# Sheet3_-_Alimentations.net
KiCad netlist of a schematic drawn in Altium Designer
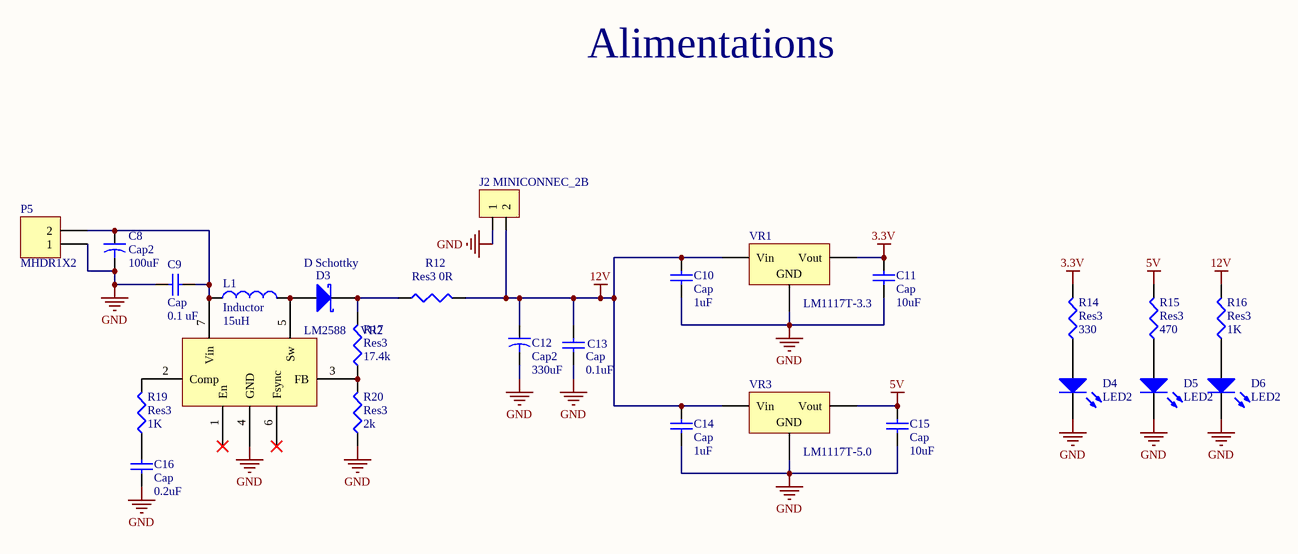
[diagram p0: Sheet3 - Alimentations.SchDoc]

(export (version "E")
  (design (tool "Eeschema 10.0.6"))
  (components
    (comp (ref "C8")
      (value "Cap2")
      (footprint "CAPR5-4X5")
      (description "Capacitor")
      (fields (field (name "ALTIUM_VALUE") "100uF") (field (name "PUBLISHER") "Altium Limited"))
      (libsource (lib "Miscellaneous Devices") (part "Cap2"))
    )
    (comp (ref "C9")
      (value "Cap")
      (footprint "RAD-0.3")
      (description "Capacitor")
      (fields (field (name "ALTIUM_VALUE") "0.1 uF") (field (name "PUBLISHER") "Altium Limited"))
      (libsource (lib "Miscellaneous Devices") (part "Cap"))
    )
    (comp (ref "C10")
      (value "Cap")
      (footprint "RAD-0.3")
      (description "Capacitor")
      (fields (field (name "ALTIUM_VALUE") "1uF") (field (name "PUBLISHER") "Altium Limited"))
      (libsource (lib "Miscellaneous Devices") (part "Cap"))
    )
    (comp (ref "C11")
      (value "Cap")
      (footprint "RAD-0.3")
      (description "Capacitor")
      (fields (field (name "ALTIUM_VALUE") "10uF") (field (name "PUBLISHER") "Altium Limited"))
      (libsource (lib "Miscellaneous Devices") (part "Cap"))
    )
    (comp (ref "C12")
      (value "Cap2")
      (footprint "CAPR5-4X5")
      (description "Capacitor")
      (fields (field (name "ALTIUM_VALUE") "330uF") (field (name "PUBLISHER") "Altium Limited"))
      (libsource (lib "Miscellaneous Devices") (part "Cap2"))
    )
    (comp (ref "C13")
      (value "Cap")
      (footprint "RAD-0.3")
      (description "Capacitor")
      (fields (field (name "ALTIUM_VALUE") "0.1uF") (field (name "PUBLISHER") "Altium Limited"))
      (libsource (lib "Miscellaneous Devices") (part "Cap"))
    )
    (comp (ref "C14")
      (value "Cap")
      (footprint "RAD-0.3")
      (description "Capacitor")
      (fields (field (name "ALTIUM_VALUE") "1uF") (field (name "PUBLISHER") "Altium Limited"))
      (libsource (lib "Miscellaneous Devices") (part "Cap"))
    )
    (comp (ref "C15")
      (value "Cap")
      (footprint "RAD-0.3")
      (description "Capacitor")
      (fields (field (name "ALTIUM_VALUE") "10uF") (field (name "PUBLISHER") "Altium Limited"))
      (libsource (lib "Miscellaneous Devices") (part "Cap"))
    )
    (comp (ref "C16")
      (value "Cap")
      (footprint "RAD-0.3")
      (description "Capacitor")
      (fields (field (name "ALTIUM_VALUE") "0.2uF") (field (name "PUBLISHER") "Altium Limited"))
      (libsource (lib "Miscellaneous Devices") (part "Cap"))
    )
    (comp (ref "D3")
      (value "D Schottky")
      (footprint "DSO-C2/X2.3")
      (description "Schottky Diode")
      (fields (field (name "PUBLISHER") "Altium Limited"))
      (libsource (lib "Miscellaneous Devices") (part "D Schottky"))
    )
    (comp (ref "D4")
      (value "LED2")
      (footprint "DSO-F2/D6.1")
      (description "Typical RED, GREEN, YELLOW, AMBER GaAs LED")
      (fields (field (name "PUBLISHER") "Altium Limited"))
      (libsource (lib "Miscellaneous Devices") (part "LED2"))
    )
    (comp (ref "D5")
      (value "LED2")
      (footprint "DSO-F2/D6.1")
      (description "Typical RED, GREEN, YELLOW, AMBER GaAs LED")
      (fields (field (name "PUBLISHER") "Altium Limited"))
      (libsource (lib "Miscellaneous Devices") (part "LED2"))
    )
    (comp (ref "D6")
      (value "LED2")
      (footprint "DSO-F2/D6.1")
      (description "Typical RED, GREEN, YELLOW, AMBER GaAs LED")
      (fields (field (name "PUBLISHER") "Altium Limited"))
      (libsource (lib "Miscellaneous Devices") (part "LED2"))
    )
    (comp (ref "J2")
      (value "MINICONNEC_2B")
      (footprint "MINICONNEC_C")
      (description "Connecteur")
      (libsource (lib "lib_peb_1") (part "MINICONNEC_2B"))
    )
    (comp (ref "L1")
      (value "Inductor")
      (footprint "INDC1005AL")
      (fields (field (name "ALTIUM_VALUE") "15uH") (field (name "PUBLISHER") "Altium Limited"))
      (libsource (lib "Miscellaneous Devices") (part "Inductor"))
    )
    (comp (ref "P5")
      (value "MHDR1X2")
      (footprint "MHDR1X2")
      (description "Header, 2-Pin")
      (fields (field (name "PUBLISHER") "Altium Limited"))
      (libsource (lib "Miscellaneous Connectors") (part "MHDR1X2"))
    )
    (comp (ref "R12")
      (value "Res3")
      (footprint "RESC1608L")
      (description "Resistor")
      (fields (field (name "ALTIUM_VALUE") "0R") (field (name "PUBLISHER") "Altium Limited"))
      (libsource (lib "Miscellaneous Devices") (part "Res3"))
    )
    (comp (ref "R14")
      (value "Res3")
      (footprint "RESC1608L")
      (description "Resistor")
      (fields (field (name "ALTIUM_VALUE") "330") (field (name "PUBLISHER") "Altium Limited"))
      (libsource (lib "Miscellaneous Devices") (part "Res3"))
    )
    (comp (ref "R15")
      (value "Res3")
      (footprint "RESC1608L")
      (description "Resistor")
      (fields (field (name "ALTIUM_VALUE") "470") (field (name "PUBLISHER") "Altium Limited"))
      (libsource (lib "Miscellaneous Devices") (part "Res3"))
    )
    (comp (ref "R16")
      (value "Res3")
      (footprint "RESC1608L")
      (description "Resistor")
      (fields (field (name "ALTIUM_VALUE") "1K") (field (name "PUBLISHER") "Altium Limited"))
      (libsource (lib "Miscellaneous Devices") (part "Res3"))
    )
    (comp (ref "R17")
      (value "Res3")
      (footprint "RESC1608L")
      (description "Resistor")
      (fields (field (name "ALTIUM_VALUE") "17.4k") (field (name "PUBLISHER") "Altium Limited"))
      (libsource (lib "Miscellaneous Devices") (part "Res3"))
    )
    (comp (ref "R19")
      (value "Res3")
      (footprint "RESC1608L")
      (description "Resistor")
      (fields (field (name "ALTIUM_VALUE") "1K") (field (name "PUBLISHER") "Altium Limited"))
      (libsource (lib "Miscellaneous Devices") (part "Res3"))
    )
    (comp (ref "R20")
      (value "Res3")
      (footprint "RESC1608L")
      (description "Resistor")
      (fields (field (name "ALTIUM_VALUE") "2k") (field (name "PUBLISHER") "Altium Limited"))
      (libsource (lib "Miscellaneous Devices") (part "Res3"))
    )
    (comp (ref "VR1")
      (value "LM1117T-3.3")
      (footprint "TO254P1510-3_4N")
      (description "Voltage Regulator")
      (fields (field (name "PUBLISHER") "Altium Limited"))
      (libsource (lib "Miscellaneous Devices") (part "Volt Reg"))
    )
    (comp (ref "VR2") (value "LM2588") (libsource (lib "lib_peb_1") (part "LM2588")))
    (comp (ref "VR3")
      (value "LM1117T-5.0")
      (footprint "TO254P1510-3_4N")
      (description "Voltage Regulator")
      (fields (field (name "PUBLISHER") "Altium Limited"))
      (libsource (lib "Miscellaneous Devices") (part "Volt Reg"))
    )
  )
  (nets
    (net (code "1") (name "3.3V") (class "Default")
      (node (ref "C11") (pin "2") (pinfunction "2_2") (pintype "passive"))
      (node (ref "R14") (pin "2") (pinfunction "2_2") (pintype "passive"))
      (node (ref "VR1") (pin "3") (pinfunction "Vout_3") (pintype "passive"))
    )
    (net (code "2") (name "5V") (class "Default")
      (node (ref "C15") (pin "2") (pinfunction "2_2") (pintype "passive"))
      (node (ref "R15") (pin "2") (pinfunction "2_2") (pintype "passive"))
      (node (ref "VR3") (pin "3") (pinfunction "Vout_3") (pintype "passive"))
    )
    (net (code "3") (name "12V") (class "Default")
      (node (ref "C10") (pin "2") (pinfunction "2_2") (pintype "passive"))
      (node (ref "C12") (pin "1") (pinfunction "1_1") (pintype "passive"))
      (node (ref "C13") (pin "2") (pinfunction "2_2") (pintype "passive"))
      (node (ref "C14") (pin "2") (pinfunction "2_2") (pintype "passive"))
      (node (ref "J2") (pin "2") (pinfunction "2_2") (pintype "passive"))
      (node (ref "R12") (pin "2") (pinfunction "2_2") (pintype "passive"))
      (node (ref "R16") (pin "2") (pinfunction "2_2") (pintype "passive"))
      (node (ref "VR1") (pin "1") (pinfunction "Vin_1") (pintype "passive"))
      (node (ref "VR3") (pin "1") (pinfunction "Vin_1") (pintype "passive"))
    )
    (net (code "4") (name "GND") (class "Default")
      (node (ref "C10") (pin "1") (pinfunction "1_1") (pintype "passive"))
      (node (ref "C11") (pin "1") (pinfunction "1_1") (pintype "passive"))
      (node (ref "C12") (pin "2") (pinfunction "2_2") (pintype "passive"))
      (node (ref "C13") (pin "1") (pinfunction "1_1") (pintype "passive"))
      (node (ref "C14") (pin "1") (pinfunction "1_1") (pintype "passive"))
      (node (ref "C15") (pin "1") (pinfunction "1_1") (pintype "passive"))
      (node (ref "C16") (pin "1") (pinfunction "1_1") (pintype "passive"))
      (node (ref "C8") (pin "2") (pinfunction "2_2") (pintype "passive"))
      (node (ref "C9") (pin "1") (pinfunction "1_1") (pintype "passive"))
      (node (ref "D4") (pin "2") (pinfunction "K_2") (pintype "passive"))
      (node (ref "D5") (pin "2") (pinfunction "K_2") (pintype "passive"))
      (node (ref "D6") (pin "2") (pinfunction "K_2") (pintype "passive"))
      (node (ref "J2") (pin "1") (pinfunction "1_1") (pintype "passive"))
      (node (ref "P5") (pin "1") (pinfunction "1_1") (pintype "passive"))
      (node (ref "R20") (pin "1") (pinfunction "1_1") (pintype "passive"))
      (node (ref "VR1") (pin "2") (pinfunction "GND_2") (pintype "passive"))
      (node (ref "VR2") (pin "4") (pinfunction "GND_4") (pintype "passive"))
      (node (ref "VR3") (pin "2") (pinfunction "GND_2") (pintype "passive"))
    )
    (net (code "5") (name "Net-(C16-Pad2)") (class "Default")
      (node (ref "C16") (pin "2") (pinfunction "2_2") (pintype "passive"))
      (node (ref "R19") (pin "1") (pinfunction "1_1") (pintype "passive"))
    )
    (net (code "6") (name "Net-(D3-A)") (class "Default")
      (node (ref "D3") (pin "1") (pinfunction "A_1") (pintype "passive"))
      (node (ref "L1") (pin "2") (pinfunction "2_2") (pintype "passive"))
      (node (ref "VR2") (pin "5") (pinfunction "Sw_5") (pintype "passive"))
    )
    (net (code "7") (name "Net-(D3-K)") (class "Default")
      (node (ref "D3") (pin "2") (pinfunction "K_2") (pintype "passive"))
      (node (ref "R12") (pin "1") (pinfunction "1_1") (pintype "passive"))
      (node (ref "R17") (pin "2") (pinfunction "2_2") (pintype "passive"))
    )
    (net (code "8") (name "Net-(D4-A)") (class "Default")
      (node (ref "D4") (pin "1") (pinfunction "A_1") (pintype "passive"))
      (node (ref "R14") (pin "1") (pinfunction "1_1") (pintype "passive"))
    )
    (net (code "9") (name "Net-(D5-A)") (class "Default")
      (node (ref "D5") (pin "1") (pinfunction "A_1") (pintype "passive"))
      (node (ref "R15") (pin "1") (pinfunction "1_1") (pintype "passive"))
    )
    (net (code "10") (name "Net-(D6-A)") (class "Default")
      (node (ref "D6") (pin "1") (pinfunction "A_1") (pintype "passive"))
      (node (ref "R16") (pin "1") (pinfunction "1_1") (pintype "passive"))
    )
    (net (code "11") (name "Net-(VR2-Comp)") (class "Default")
      (node (ref "R19") (pin "2") (pinfunction "2_2") (pintype "passive"))
      (node (ref "VR2") (pin "2") (pinfunction "Comp_2") (pintype "passive"))
    )
    (net (code "12") (name "Net-(VR2-FB)") (class "Default")
      (node (ref "R17") (pin "1") (pinfunction "1_1") (pintype "passive"))
      (node (ref "R20") (pin "2") (pinfunction "2_2") (pintype "passive"))
      (node (ref "VR2") (pin "3") (pinfunction "FB_3") (pintype "passive"))
    )
    (net (code "13") (name "Net-(VR2-Vin)") (class "Default")
      (node (ref "C8") (pin "1") (pinfunction "1_1") (pintype "passive"))
      (node (ref "C9") (pin "2") (pinfunction "2_2") (pintype "passive"))
      (node (ref "L1") (pin "1") (pinfunction "1_1") (pintype "passive"))
      (node (ref "P5") (pin "2") (pinfunction "2_2") (pintype "passive"))
      (node (ref "VR2") (pin "7") (pinfunction "Vin_7") (pintype "passive"))
    )
    (net (code "14") (name "unconnected-(VR2-En-Pad1)") (class "Default")
      (node (ref "VR2") (pin "1") (pinfunction "En_1") (pintype "passive+no_connect"))
    )
    (net (code "15") (name "unconnected-(VR2-Fsync-Pad6)") (class "Default")
      (node (ref "VR2") (pin "6") (pinfunction "Fsync_6") (pintype "passive+no_connect"))
    )
  )
)
